# main_hall_crossboard_1_1.net
KiCad netlist of a schematic drawn in Altium Designer
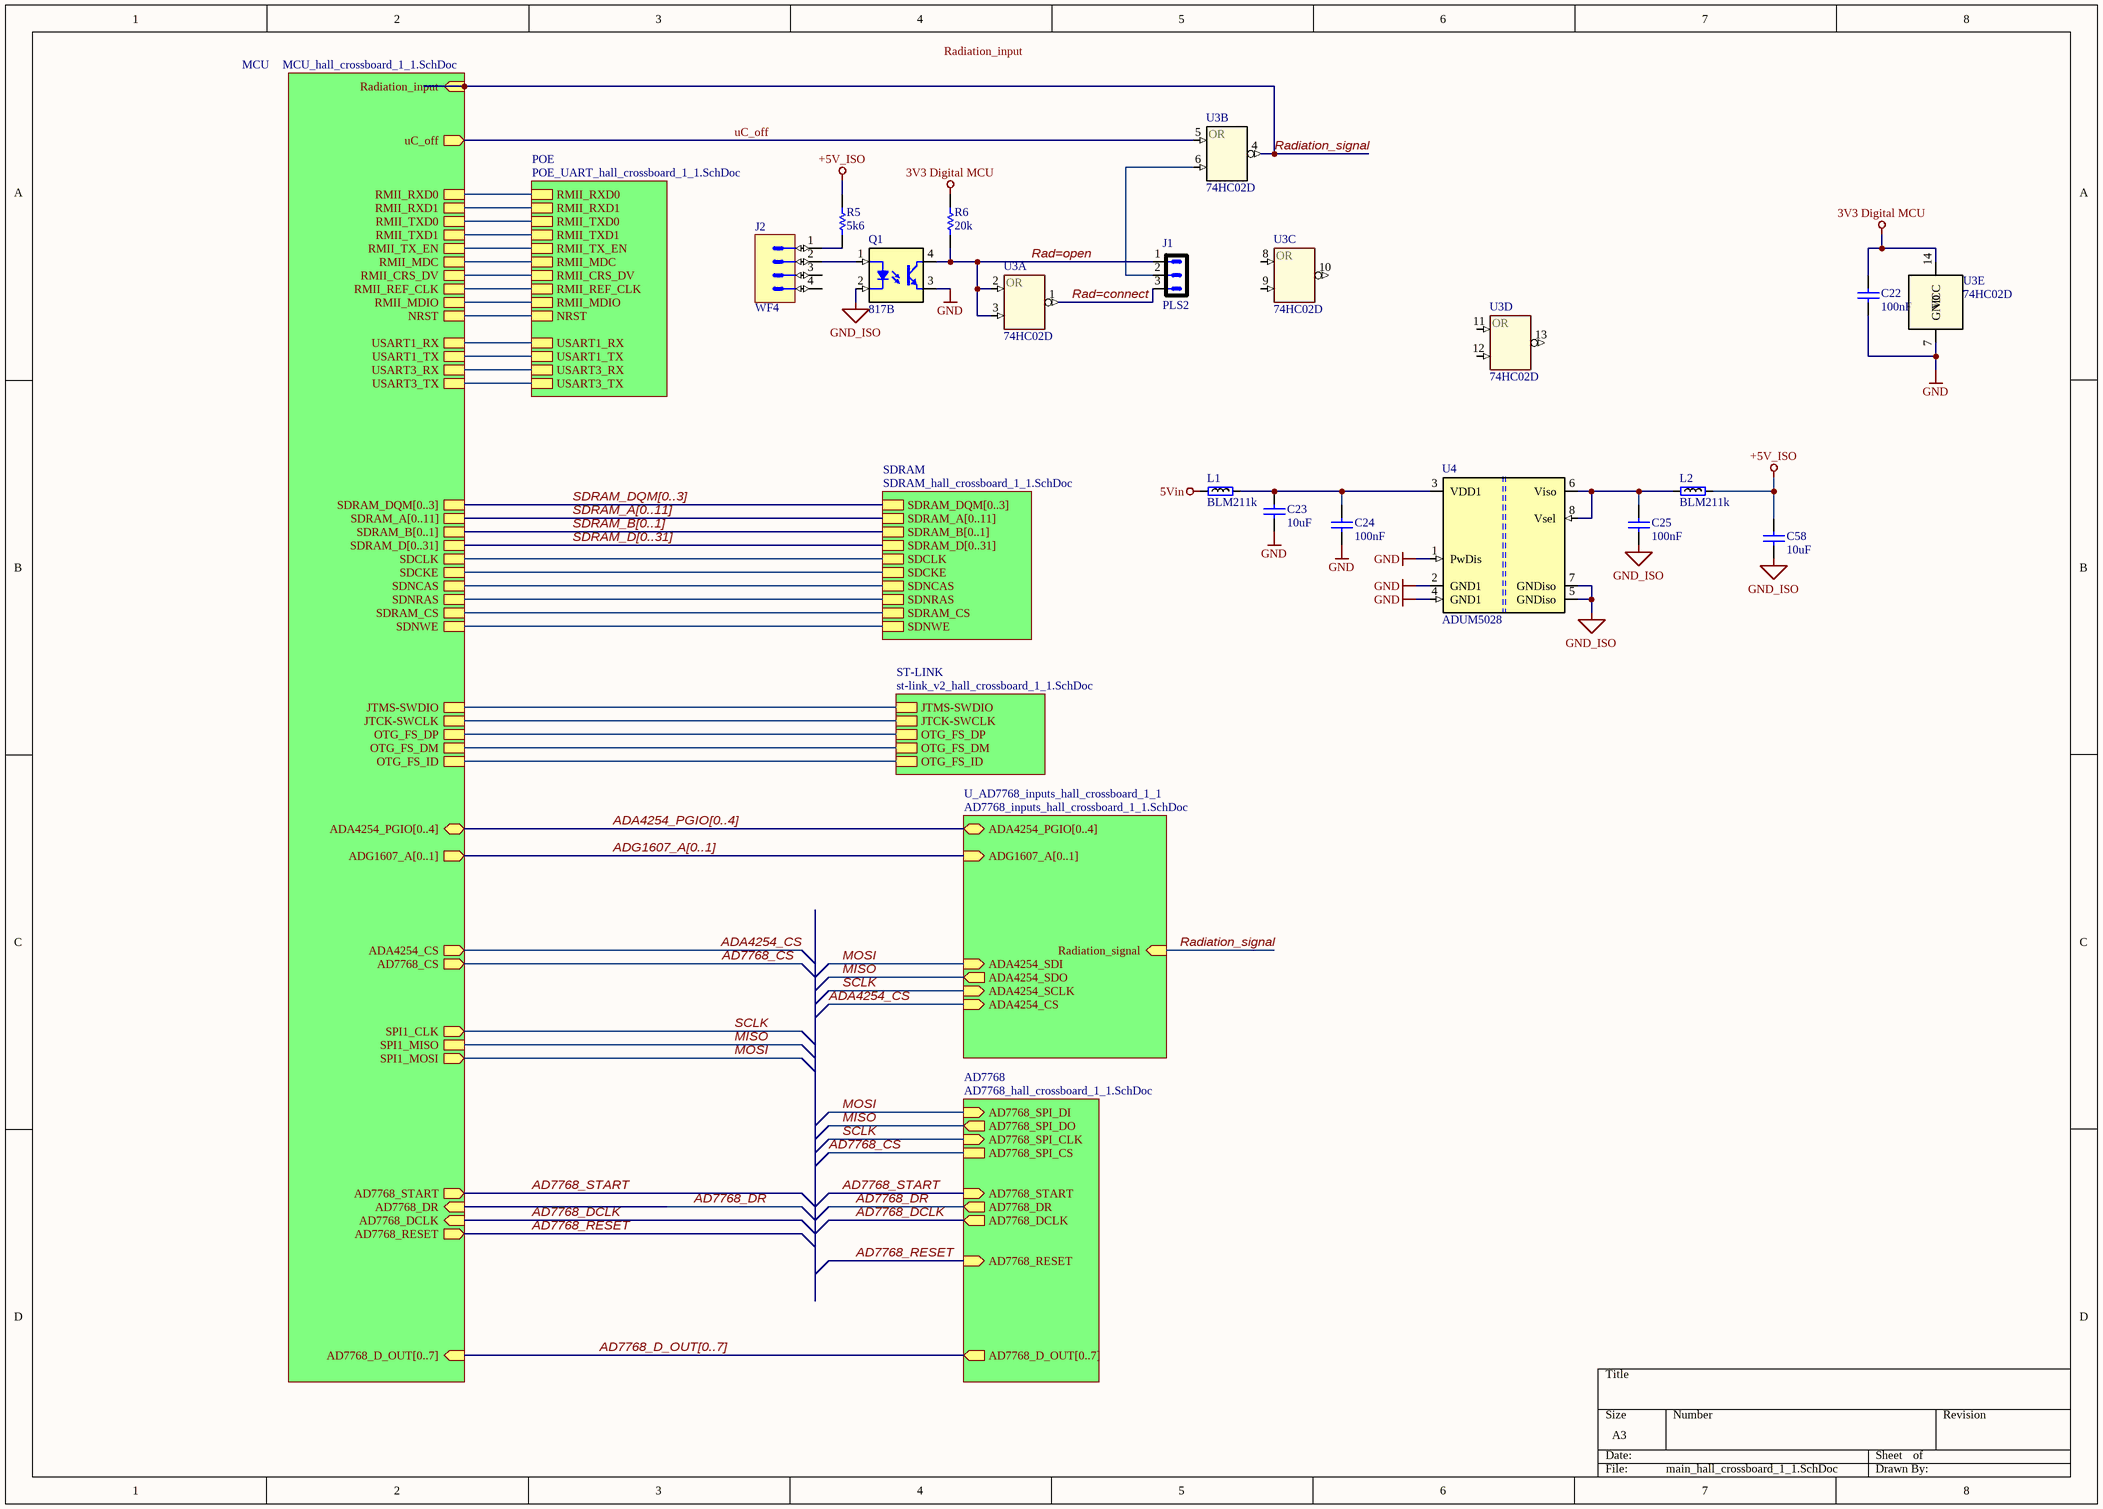
[diagram p0: main_hall_crossboard_1_1.SchDoc]

(export (version "E")
  (design (tool "Eeschema 10.0.6"))
  (components
    (comp (ref "C22")
      (value "100nF")
      (footprint "hall_crossboard_1_1_library:0603C")
      (description "Capacitor 0402 / 0603 / 0805")
      (libsource (lib "hall_crossboard_1_1_library") (part "Capacitor_ST"))
    )
    (comp (ref "C23")
      (value "10uF")
      (footprint "hall_crossboard_1_1_library:0805C")
      (description "Capacitor 0402 / 0603 / 0805")
      (libsource (lib "hall_crossboard_1_1_library") (part "Capacitor_ST"))
    )
    (comp (ref "C24")
      (value "100nF")
      (footprint "hall_crossboard_1_1_library:0603C")
      (description "Capacitor 0402 / 0603 / 0805")
      (libsource (lib "hall_crossboard_1_1_library") (part "Capacitor_ST"))
    )
    (comp (ref "C25")
      (value "100nF")
      (footprint "hall_crossboard_1_1_library:0603C")
      (description "Capacitor 0402 / 0603 / 0805")
      (libsource (lib "hall_crossboard_1_1_library") (part "Capacitor_ST"))
    )
    (comp (ref "C58")
      (value "10uF")
      (footprint "hall_crossboard_1_1_library:0805C")
      (description "Capacitor 0402 / 0603 / 0805")
      (libsource (lib "hall_crossboard_1_1_library") (part "Capacitor_ST"))
    )
    (comp (ref "J1")
      (value "PLS2")
      (footprint "COMATEL_385.0358.1.03.400")
      (description "PLS3")
      (libsource (lib "hall_crossboard_1_1") (part "PLS3"))
    )
    (comp (ref "J2")
      (value "WF4")
      (footprint "hall_crossboard_1_1_library:WF4_2_54")
      (description "Вилка  WF4")
      (libsource (lib "schematic_hall_crossboard_1_1_library") (part "WF4"))
    )
    (comp (ref "L1")
      (value "BLM211k")
      (footprint "footprint_hall_crossboard_1_1_library:RESC2012X50N")
      (description "SMD Ferrite bead 0805")
      (libsource (lib "schematic_hall_crossboard_1_1_library") (part "BLM21"))
    )
    (comp (ref "L2")
      (value "BLM211k")
      (footprint "footprint_hall_crossboard_1_1_library:RESC2012X50N")
      (description "SMD Ferrite bead 0805")
      (libsource (lib "schematic_hall_crossboard_1_1_library") (part "BLM21"))
    )
    (comp (ref "Q1")
      (value "817B")
      (footprint "DIP4-300")
      (description "Optotransistor")
      (fields (field (name "VOLTAGE") "35V"))
      (libsource (lib "schematic_hall_crossboard_1_1_library") (part "817B"))
    )
    (comp (ref "R5")
      (value "5k6")
      (footprint "0603R")
      (description "Resistor 0402 / 0603 / 0805 c2")
      (libsource (lib "hall_crossboard_1_1") (part "Resistor_ST"))
    )
    (comp (ref "R6")
      (value "20k")
      (footprint "0603R")
      (description "Resistor 0402 / 0603 / 0805 c2")
      (libsource (lib "hall_crossboard_1_1") (part "Resistor_ST"))
    )
    (comp (ref "U3")
      (value "74HC02D")
      (footprint "SOIC127P600X175-14N")
      (description "4 лог. элемента 2ИЛИ-НЕ")
      (fields (field (name "VOLTAGE") "2.. 6V"))
      (libsource (lib "hall_crossboard_1_1") (part "74HC02D"))
    )
    (comp (ref "U4")
      (value "ADUM5028")
      (footprint "hall_crossboard_1_1_library:SOIC127P600X175-8N")
      (description "Isolateted DC DC 5V->5V or 3V3 60mA")
      (libsource (lib "DDSintLib") (part "ADUM5028"))
    )
  )
  (nets
    (net (code "66") (name "+5V_ISO") (class "Default")
      (node (ref "C58") (pin "2") (pinfunction "2_2") (pintype "passive"))
      (node (ref "L2") (pin "1") (pinfunction "1_1") (pintype "passive"))
      (node (ref "R5") (pin "2") (pinfunction "2_2") (pintype "passive"))
    )
    (net (code "93") (name "/Rad=connect") (class "Default")
      (node (ref "J1") (pin "3") (pinfunction "3_3") (pintype "bidirectional"))
      (node (ref "U3") (pin "1") (pinfunction "OUT_1") (pintype "output"))
    )
    (net (code "94") (name "/Rad=open") (class "Default")
      (node (ref "J1") (pin "1") (pinfunction "1_1") (pintype "bidirectional"))
      (node (ref "Q1") (pin "4") (pinfunction "C_4") (pintype "open_collector"))
      (node (ref "R6") (pin "1") (pinfunction "1_1") (pintype "passive"))
      (node (ref "U3") (pin "2") (pinfunction "IN_2") (pintype "input"))
      (node (ref "U3") (pin "3") (pinfunction "IN_3") (pintype "input"))
    )
    (net (code "96") (name "/Radiation_signal") (class "Default")
      (node (ref "U3") (pin "4") (pinfunction "OUT_4") (pintype "output"))
    )
    (net (code "112") (name "/uC_off") (class "Default")
      (node (ref "U3") (pin "5") (pinfunction "IN_5") (pintype "input"))
    )
    (net (code "113") (name "3V3 Digital MCU") (class "Default")
      (node (ref "C22") (pin "2") (pinfunction "2_2") (pintype "passive"))
      (node (ref "R6") (pin "2") (pinfunction "2_2") (pintype "passive"))
      (node (ref "U3") (pin "14") (pinfunction "VCC_14") (pintype "power_in"))
    )
    (net (code "114") (name "5Vin") (class "Default")
      (node (ref "L1") (pin "2") (pinfunction "2_2") (pintype "passive"))
    )
    (net (code "115") (name "GND") (class "Default")
      (node (ref "C22") (pin "1") (pinfunction "1_1") (pintype "passive"))
      (node (ref "C23") (pin "1") (pinfunction "1_1") (pintype "passive"))
      (node (ref "C24") (pin "1") (pinfunction "1_1") (pintype "passive"))
      (node (ref "Q1") (pin "3") (pinfunction "E_3") (pintype "open_emitter"))
      (node (ref "U3") (pin "7") (pinfunction "GND_7") (pintype "power_in"))
      (node (ref "U4") (pin "1") (pinfunction "PwDis_1") (pintype "input"))
      (node (ref "U4") (pin "2") (pinfunction "GND1_2") (pintype "power_in"))
      (node (ref "U4") (pin "4") (pinfunction "GND1_4") (pintype "input"))
    )
    (net (code "116") (name "GND_ISO") (class "Default")
      (node (ref "C25") (pin "1") (pinfunction "1_1") (pintype "passive"))
      (node (ref "C58") (pin "1") (pinfunction "1_1") (pintype "passive"))
      (node (ref "Q1") (pin "2") (pinfunction "C_2") (pintype "input"))
      (node (ref "U4") (pin "5") (pinfunction "GNDiso_5") (pintype "power_in"))
      (node (ref "U4") (pin "7") (pinfunction "GNDiso_7") (pintype "power_in"))
    )
    (net (code "117") (name "Net-(J1-Pad2)") (class "Default")
      (node (ref "J1") (pin "2") (pinfunction "2_2") (pintype "bidirectional"))
      (node (ref "U3") (pin "6") (pinfunction "IN_6") (pintype "input"))
    )
    (net (code "118") (name "Net-(J2-Pad1)") (class "Default")
      (node (ref "J2") (pin "1") (pinfunction "1_1") (pintype "bidirectional"))
      (node (ref "R5") (pin "1") (pinfunction "1_1") (pintype "passive"))
    )
    (net (code "119") (name "Net-(Q1-A)") (class "Default")
      (node (ref "J2") (pin "2") (pinfunction "2_2") (pintype "bidirectional"))
      (node (ref "Q1") (pin "1") (pinfunction "A_1") (pintype "input"))
    )
    (net (code "120") (name "Net-(U4-VDD1)") (class "Default")
      (node (ref "C23") (pin "2") (pinfunction "2_2") (pintype "passive"))
      (node (ref "C24") (pin "2") (pinfunction "2_2") (pintype "passive"))
      (node (ref "L1") (pin "1") (pinfunction "1_1") (pintype "passive"))
      (node (ref "U4") (pin "3") (pinfunction "VDD1_3") (pintype "power_in"))
    )
    (net (code "121") (name "Net-(U4-Viso)") (class "Default")
      (node (ref "C25") (pin "2") (pinfunction "2_2") (pintype "passive"))
      (node (ref "L2") (pin "2") (pinfunction "2_2") (pintype "passive"))
      (node (ref "U4") (pin "6") (pinfunction "Viso_6") (pintype "power_in"))
      (node (ref "U4") (pin "8") (pinfunction "Vsel_8") (pintype "input"))
    )
    (net (code "122") (name "unconnected-(J2-Pad3)") (class "Default")
      (node (ref "J2") (pin "3") (pinfunction "3_3") (pintype "bidirectional"))
    )
    (net (code "123") (name "unconnected-(J2-Pad4)") (class "Default")
      (node (ref "J2") (pin "4") (pinfunction "4_4") (pintype "bidirectional"))
    )
    (net (code "124") (name "unconnected-(U3C-IN-Pad8)") (class "Default")
      (node (ref "U3") (pin "8") (pinfunction "IN_8") (pintype "input"))
    )
    (net (code "125") (name "unconnected-(U3C-IN-Pad9)") (class "Default")
      (node (ref "U3") (pin "9") (pinfunction "IN_9") (pintype "input"))
    )
    (net (code "126") (name "unconnected-(U3C-OUT-Pad10)") (class "Default")
      (node (ref "U3") (pin "10") (pinfunction "OUT_10") (pintype "output"))
    )
    (net (code "127") (name "unconnected-(U3D-IN-Pad11)") (class "Default")
      (node (ref "U3") (pin "11") (pinfunction "IN_11") (pintype "input"))
    )
    (net (code "128") (name "unconnected-(U3D-IN-Pad12)") (class "Default")
      (node (ref "U3") (pin "12") (pinfunction "IN_12") (pintype "input"))
    )
    (net (code "129") (name "unconnected-(U3D-OUT-Pad13)") (class "Default")
      (node (ref "U3") (pin "13") (pinfunction "OUT_13") (pintype "output"))
    )
  )
)
